# Sheet4_PSU.net
KiCad netlist of a schematic drawn in Altium Designer
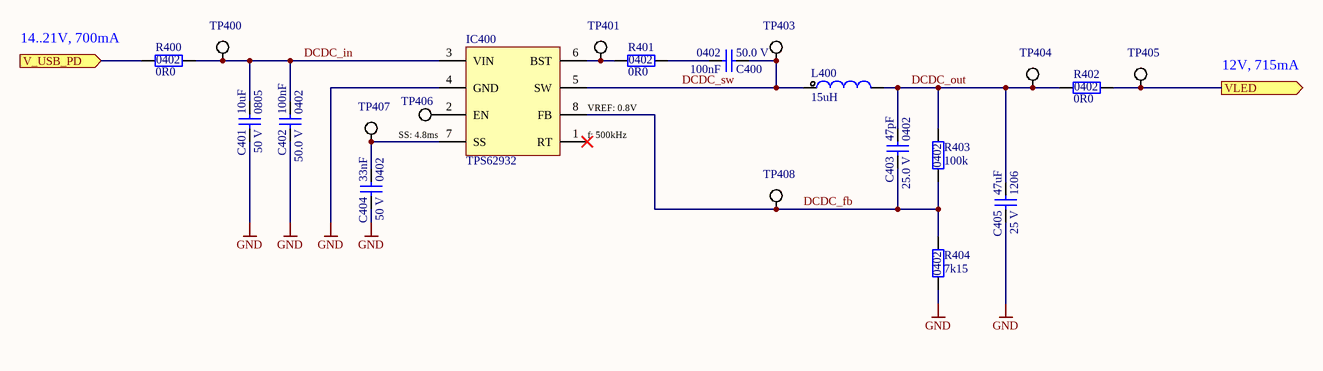
[diagram p0: Sheet4_PSU.SchDoc]

(export (version "E")
  (design (tool "Eeschema 10.0.6"))
  (components
    (comp (ref "C400")
      (value "C 100nF 0402 50V")
      (footprint "0402")
      (description "CAP CER 0.1UF 50V X7R 0402")
      (fields
        (field (name "MANUFACTURER") "Murata Electronics")
        (field (name "MANUFACTURER PART NUMBER") "GRM155R71H104KE14J")
        (field (name "CAPACITANCE") "100nF")
        (field (name "VOLTAGE") "50.0 V")
      )
      (libsource (lib "CS_Part_Library") (part "CAP_100nF_50V_0402"))
    )
    (comp (ref "C401")
      (value "C 10uF 0805 50V")
      (footprint "0805")
      (description "CAP CER 10UF 50V X5R 0805")
      (fields
        (field (name "MANUFACTURER") "Murata Electronics")
        (field (name "MANUFACTURER PART NUMBER") "GRM21BR61H106KE43K")
        (field (name "CAPACITANCE") "10uF")
        (field (name "VOLTAGE") "50 V")
      )
      (libsource (lib "CS_Part_Library") (part "CAP_10uF_50V_0805"))
    )
    (comp (ref "C402")
      (value "C 100nF 0402 50V")
      (footprint "0402")
      (description "CAP CER 0.1UF 50V X7R 0402")
      (fields
        (field (name "MANUFACTURER") "Murata Electronics")
        (field (name "MANUFACTURER PART NUMBER") "GRM155R71H104KE14J")
        (field (name "CAPACITANCE") "100nF")
        (field (name "VOLTAGE") "50.0 V")
      )
      (libsource (lib "CS_Part_Library") (part "CAP_100nF_50V_0402"))
    )
    (comp (ref "C403")
      (value "C 47pF 0402 25V")
      (footprint "0402")
      (description "CAP CER 47PF 25V C0G/NP0 0402")
      (fields
        (field (name "MANUFACTURER") "KEMET")
        (field (name "MANUFACTURER PART NUMBER") "C0402C470J3GAC7867")
        (field (name "CAPACITANCE") "47pF")
        (field (name "VOLTAGE") "25.0 V")
      )
      (libsource (lib "CS_Part_Library") (part "CAP_47pF_25V_0402"))
    )
    (comp (ref "C404")
      (value "C 33nF 0402 50V")
      (footprint "0402")
      (description "CAP CER 0.033UF 50V X7R 0402")
      (fields
        (field (name "MANUFACTURER") "Murata Electronics")
        (field (name "MANUFACTURER PART NUMBER") "GCM155R71H333KE02J")
        (field (name "CAPACITANCE") "33nF")
        (field (name "VOLTAGE") "50 V")
      )
      (libsource (lib "CS_Part_Library") (part "CAP_33nF_50V_0402"))
    )
    (comp (ref "C405")
      (value "C 47uF 1206 25V")
      (footprint "1206")
      (description "CAP CER 47UF 25V X5R 1206")
      (fields
        (field (name "MANUFACTURER") "Murata Electronics")
        (field (name "MANUFACTURER PART NUMBER") "GRM31CR61E476ME44K")
        (field (name "CAPACITANCE") "47uF")
        (field (name "VOLTAGE") "25 V")
      )
      (libsource (lib "CS_Part_Library") (part "CAP_47uF_25V_1206"))
    )
    (comp (ref "IC400")
      (value "TPS62932")
      (footprint "SOT-583")
      (description "IC REG BUCK ADJ 2A SOT583")
      (fields
        (field (name "MANUFACTURER") "Texas Instruments")
        (field (name "MANUFACTURER PART NUMBER") "TPS62932DRLR")
      )
      (libsource (lib "CS_Part_Library") (part "IC_Reg_TPS62932DRLR"))
    )
    (comp (ref "L400")
      (value "L 15uH 6.5A")
      (footprint "L_7447709150")
      (description "FIXED IND 15UH 6.5A 26 MOHM SMD")
      (fields
        (field (name "MANUFACTURER") "Würth Elektronik")
        (field (name "MANUFACTURER PART NUMBER") "7447709150")
        (field (name "INDUCTANCE") "15uH")
      )
      (libsource (lib "CS_Part_Library") (part "L_15uH_6.5A"))
    )
    (comp (ref "R400")
      (value "R 0R0 0402")
      (footprint "0402")
      (description "RES 0 OHM JUMPER 1/16W 0402")
      (fields
        (field (name "MANUFACTURER") "Stackpole Electronics Inc")
        (field (name "MANUFACTURER PART NUMBER") "RMCF0402ZT0R00")
        (field (name "RESISTANCE") "0R0")
      )
      (libsource (lib "CS_Part_Library") (part "R_0R0_0402"))
    )
    (comp (ref "R401")
      (value "R 0R0 0402")
      (footprint "0402")
      (description "RES 0 OHM JUMPER 1/16W 0402")
      (fields
        (field (name "MANUFACTURER") "Stackpole Electronics Inc")
        (field (name "MANUFACTURER PART NUMBER") "RMCF0402ZT0R00")
        (field (name "RESISTANCE") "0R0")
      )
      (libsource (lib "CS_Part_Library") (part "R_0R0_0402"))
    )
    (comp (ref "R402")
      (value "R 0R0 0402")
      (footprint "0402")
      (description "RES 0 OHM JUMPER 1/16W 0402")
      (fields
        (field (name "MANUFACTURER") "Stackpole Electronics Inc")
        (field (name "MANUFACTURER PART NUMBER") "RMCF0402ZT0R00")
        (field (name "RESISTANCE") "0R0")
      )
      (libsource (lib "CS_Part_Library") (part "R_0R0_0402"))
    )
    (comp (ref "R403")
      (value "R 100k 0402")
      (footprint "0402")
      (description "RES 100K OHM 5% 1/16W 0402")
      (fields
        (field (name "MANUFACTURER") "YAGEO")
        (field (name "MANUFACTURER PART NUMBER") "RC0402JR-07100KL")
        (field (name "RESISTANCE") "100k")
      )
      (libsource (lib "CS_Part_Library") (part "R_100k_0402"))
    )
    (comp (ref "R404")
      (value "R 7k15 0402")
      (footprint "0402")
      (description "RES 7.15K OHM 1% 1/16W 0402")
      (fields
        (field (name "MANUFACTURER") "Stackpole Electronics Inc")
        (field (name "MANUFACTURER PART NUMBER") "RMCF0402FT7K15")
        (field (name "RESISTANCE") "7k15")
      )
      (libsource (lib "CS_Part_Library") (part "R_7k15_0402"))
    )
    (comp (ref "TP400")
      (value "TP")
      (footprint "TP_1mm")
      (description "Test Point 1mm")
      (libsource (lib "Symbols") (part "TP_1mm"))
    )
    (comp (ref "TP401")
      (value "TP")
      (footprint "TP_1mm")
      (description "Test Point 1mm")
      (libsource (lib "Symbols") (part "TP_1mm"))
    )
    (comp (ref "TP403")
      (value "TP")
      (footprint "TP_1mm")
      (description "Test Point 1mm")
      (libsource (lib "Symbols") (part "TP_1mm"))
    )
    (comp (ref "TP404")
      (value "TP")
      (footprint "TP_1mm")
      (description "Test Point 1mm")
      (libsource (lib "Symbols") (part "TP_1mm"))
    )
    (comp (ref "TP405")
      (value "TP")
      (footprint "TP_1mm")
      (description "Test Point 1mm")
      (libsource (lib "Symbols") (part "TP_1mm"))
    )
    (comp (ref "TP406")
      (value "TP")
      (footprint "TP_1mm")
      (description "Test Point 1mm")
      (libsource (lib "Symbols") (part "TP_1mm"))
    )
    (comp (ref "TP407")
      (value "TP")
      (footprint "TP_1mm")
      (description "Test Point 1mm")
      (libsource (lib "Symbols") (part "TP_1mm"))
    )
    (comp (ref "TP408")
      (value "TP")
      (footprint "TP_1mm")
      (description "Test Point 1mm")
      (libsource (lib "Symbols") (part "TP_1mm"))
    )
  )
  (nets
    (net (code "1") (name "/DCDC_fb") (class "Default")
      (node (ref "C403") (pin "1") (pinfunction "1_1") (pintype "passive"))
      (node (ref "IC400") (pin "8") (pinfunction "FB_8") (pintype "passive"))
      (node (ref "R403") (pin "1") (pinfunction "1_1") (pintype "passive"))
      (node (ref "R404") (pin "2") (pinfunction "2_2") (pintype "passive"))
      (node (ref "TP408") (pin "1") (pinfunction "TP_1") (pintype "passive"))
    )
    (net (code "2") (name "/DCDC_in") (class "Default")
      (node (ref "C401") (pin "2") (pinfunction "2_2") (pintype "passive"))
      (node (ref "C402") (pin "2") (pinfunction "2_2") (pintype "passive"))
      (node (ref "IC400") (pin "3") (pinfunction "VIN_3") (pintype "passive"))
      (node (ref "R400") (pin "2") (pinfunction "2_2") (pintype "passive"))
      (node (ref "TP400") (pin "1") (pinfunction "TP_1") (pintype "passive"))
    )
    (net (code "3") (name "/DCDC_out") (class "Default")
      (node (ref "C403") (pin "2") (pinfunction "2_2") (pintype "passive"))
      (node (ref "C405") (pin "2") (pinfunction "2_2") (pintype "passive"))
      (node (ref "L400") (pin "2") (pinfunction "2_2") (pintype "passive"))
      (node (ref "R402") (pin "1") (pinfunction "1_1") (pintype "passive"))
      (node (ref "R403") (pin "2") (pinfunction "2_2") (pintype "passive"))
      (node (ref "TP404") (pin "1") (pinfunction "TP_1") (pintype "passive"))
    )
    (net (code "4") (name "/DCDC_sw") (class "Default")
      (node (ref "C400") (pin "1") (pinfunction "1_1") (pintype "passive"))
      (node (ref "IC400") (pin "5") (pinfunction "SW_5") (pintype "passive"))
      (node (ref "L400") (pin "1") (pinfunction "1_1") (pintype "passive"))
      (node (ref "TP403") (pin "1") (pinfunction "TP_1") (pintype "passive"))
    )
    (net (code "5") (name "/VLED") (class "Default")
      (node (ref "R402") (pin "2") (pinfunction "2_2") (pintype "passive"))
      (node (ref "TP405") (pin "1") (pinfunction "TP_1") (pintype "passive"))
    )
    (net (code "6") (name "/V_USB_PD") (class "Default")
      (node (ref "R400") (pin "1") (pinfunction "1_1") (pintype "passive"))
    )
    (net (code "7") (name "GND") (class "Default")
      (node (ref "C401") (pin "1") (pinfunction "1_1") (pintype "passive"))
      (node (ref "C402") (pin "1") (pinfunction "1_1") (pintype "passive"))
      (node (ref "C404") (pin "1") (pinfunction "1_1") (pintype "passive"))
      (node (ref "C405") (pin "1") (pinfunction "1_1") (pintype "passive"))
      (node (ref "IC400") (pin "4") (pinfunction "GND_4") (pintype "passive"))
      (node (ref "R404") (pin "1") (pinfunction "1_1") (pintype "passive"))
    )
    (net (code "8") (name "Net-(C400-Pad2)") (class "Default")
      (node (ref "C400") (pin "2") (pinfunction "2_2") (pintype "passive"))
      (node (ref "R401") (pin "2") (pinfunction "2_2") (pintype "passive"))
    )
    (net (code "9") (name "Net-(IC400-BST)") (class "Default")
      (node (ref "IC400") (pin "6") (pinfunction "BST_6") (pintype "passive"))
      (node (ref "R401") (pin "1") (pinfunction "1_1") (pintype "passive"))
      (node (ref "TP401") (pin "1") (pinfunction "TP_1") (pintype "passive"))
    )
    (net (code "10") (name "Net-(IC400-EN)") (class "Default")
      (node (ref "IC400") (pin "2") (pinfunction "EN_2") (pintype "passive"))
      (node (ref "TP406") (pin "1") (pinfunction "TP_1") (pintype "passive"))
    )
    (net (code "11") (name "Net-(IC400-SS)") (class "Default")
      (node (ref "C404") (pin "2") (pinfunction "2_2") (pintype "passive"))
      (node (ref "IC400") (pin "7") (pinfunction "SS_7") (pintype "passive"))
      (node (ref "TP407") (pin "1") (pinfunction "TP_1") (pintype "passive"))
    )
    (net (code "12") (name "unconnected-(IC400-RT-Pad1)") (class "Default")
      (node (ref "IC400") (pin "1") (pinfunction "RT_1") (pintype "passive+no_connect"))
    )
  )
)
